# Top.net
KiCad netlist of a schematic drawn in Altium Designer
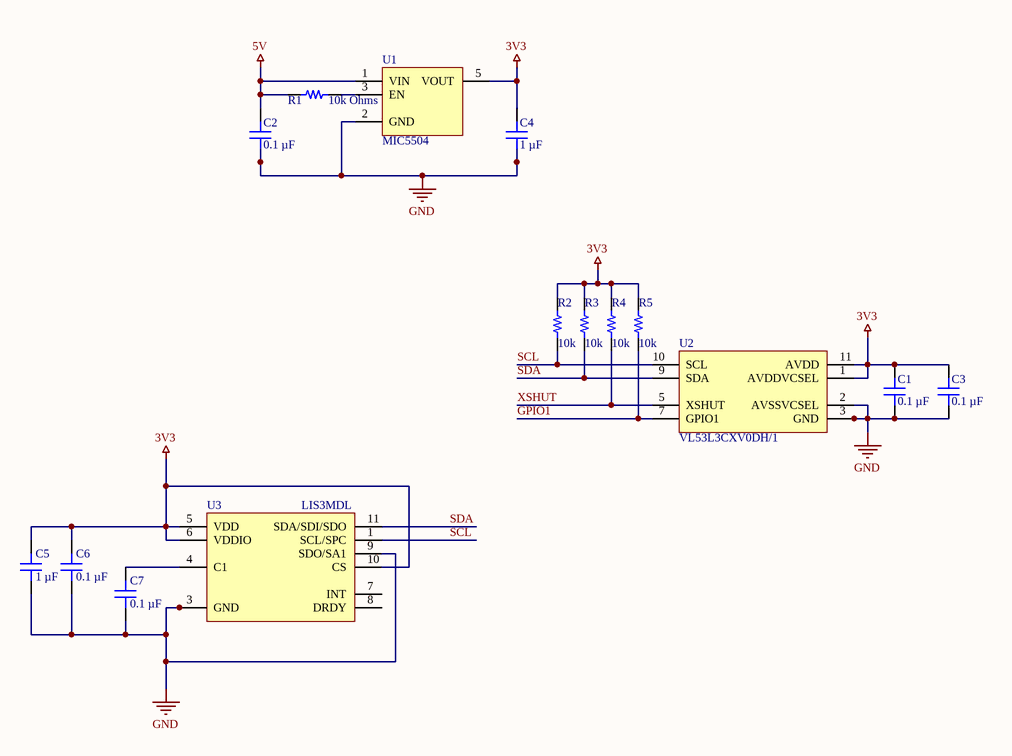
[diagram p0: Top.SchDoc]

(export (version "E")
  (design (tool "Eeschema 10.0.6"))
  (components
    (comp (ref "C1")
      (value "0.1 µF")
      (footprint "CAP 0402_1005")
      (description "CAP CER 0.1UF 16V X7R 0402")
      (fields (field (name "PART NUMBER") "C0402C104K4RACAUTO") (field (name "MANUFACTURER") "KEMET"))
      (libsource (lib "Celestial Altium Library - altium_library") (part "Capacitor"))
    )
    (comp (ref "C2")
      (value "0.1 µF")
      (footprint "CAP 0402_1005")
      (description "CAP CER 0.1UF 16V X7R 0402")
      (fields (field (name "PART NUMBER") "C0402C104K4RACAUTO") (field (name "MANUFACTURER") "KEMET"))
      (libsource (lib "Celestial Altium Library - altium_library") (part "Capacitor"))
    )
    (comp (ref "C3")
      (value "0.1 µF")
      (footprint "CAP 0402_1005")
      (description "CAP CER 0.1UF 16V X7R 0402")
      (fields (field (name "PART NUMBER") "C0402C104K4RACAUTO") (field (name "MANUFACTURER") "KEMET"))
      (libsource (lib "Celestial Altium Library - altium_library") (part "Capacitor"))
    )
    (comp (ref "C4")
      (value "1 µF")
      (footprint "CAP 0402_1005")
      (description "CAP CER 0.1UF 16V X7R 0402")
      (fields (field (name "PART NUMBER") "C0402C104K4RACAUTO") (field (name "MANUFACTURER") "KEMET"))
      (libsource (lib "Celestial Altium Library - altium_library") (part "Capacitor"))
    )
    (comp (ref "C5")
      (value "1 µF")
      (footprint "CAP 0402_1005")
      (description "CAP CER 0.1UF 16V X7R 0402")
      (fields (field (name "PART NUMBER") "C0402C104K4RACAUTO") (field (name "MANUFACTURER") "KEMET"))
      (libsource (lib "Celestial Altium Library - altium_library") (part "Capacitor"))
    )
    (comp (ref "C6")
      (value "0.1 µF")
      (footprint "CAP 0402_1005")
      (description "CAP CER 0.1UF 16V X7R 0402")
      (fields (field (name "PART NUMBER") "C0402C104K4RACAUTO") (field (name "MANUFACTURER") "KEMET"))
      (libsource (lib "Celestial Altium Library - altium_library") (part "Capacitor"))
    )
    (comp (ref "C7")
      (value "0.1 µF")
      (footprint "CAP 0402_1005")
      (description "CAP CER 0.1UF 16V X7R 0402")
      (fields (field (name "PART NUMBER") "C0402C104K4RACAUTO") (field (name "MANUFACTURER") "KEMET"))
      (libsource (lib "Celestial Altium Library - altium_library") (part "Capacitor"))
    )
    (comp (ref "R1")
      (value "10k Ohms")
      (footprint "RES 0402_1005")
      (description "RES 330 OHM 5% 1/16W 0402")
      (fields (field (name "PART NUMBER") "CRCW0402330RJNEDC") (field (name "MANUFACTURER") "Vishay Dale"))
      (libsource (lib "Celestial Altium Library - altium_library") (part "Resistor"))
    )
    (comp (ref "R2")
      (value "10k")
      (footprint "RES 0402_1005")
      (description "RES 330 OHM 5% 1/16W 0402")
      (fields (field (name "PART NUMBER") "CRCW0402330RJNEDC") (field (name "MANUFACTURER") "Vishay Dale"))
      (libsource (lib "Celestial Altium Library - altium_library") (part "Resistor"))
    )
    (comp (ref "R3")
      (value "10k")
      (footprint "RES 0402_1005")
      (description "RES 330 OHM 5% 1/16W 0402")
      (fields (field (name "PART NUMBER") "CRCW0402330RJNEDC") (field (name "MANUFACTURER") "Vishay Dale"))
      (libsource (lib "Celestial Altium Library - altium_library") (part "Resistor"))
    )
    (comp (ref "R4")
      (value "10k")
      (footprint "RES 0402_1005")
      (description "RES 330 OHM 5% 1/16W 0402")
      (fields (field (name "PART NUMBER") "CRCW0402330RJNEDC") (field (name "MANUFACTURER") "Vishay Dale"))
      (libsource (lib "Celestial Altium Library - altium_library") (part "Resistor"))
    )
    (comp (ref "R5")
      (value "10k")
      (footprint "RES 0402_1005")
      (description "RES 330 OHM 5% 1/16W 0402")
      (fields (field (name "PART NUMBER") "CRCW0402330RJNEDC") (field (name "MANUFACTURER") "Vishay Dale"))
      (libsource (lib "Celestial Altium Library - altium_library") (part "Resistor"))
    )
    (comp (ref "U1")
      (value "MIC5504")
      (footprint "TI SOT-23-5 DBV")
      (description "3.3V LDO")
      (libsource (lib "IC") (part "MIC5504-3.3YM5"))
    )
    (comp (ref "U2")
      (value "VL53L3CXV0DH/1")
      (footprint "XDCR_VL53L3CXV0DH/1")
      (description "Optical Sensor 118.110 (3m) I2C Output")
      (fields (field (name "MF") "STMicroelectronics"))
      (libsource (lib "IC") (part "VL53L3CXV0DH/1"))
    )
    (comp (ref "U3")
      (value "LIS3MDL")
      (footprint "LGA12_ST")
      (description "Magnetometer")
      (libsource (lib "IC") (part "LIS3MDL"))
    )
  )
  (nets
    (net (code "1") (name "/GPIO1") (class "Default")
      (node (ref "R5") (pin "2") (pinfunction "2_2") (pintype "passive"))
      (node (ref "U2") (pin "7") (pinfunction "GPIO1_7") (pintype "passive"))
    )
    (net (code "2") (name "/SCL") (class "Default")
      (node (ref "R2") (pin "2") (pinfunction "2_2") (pintype "passive"))
      (node (ref "U2") (pin "10") (pinfunction "SCL_10") (pintype "passive"))
      (node (ref "U3") (pin "1") (pinfunction "SCL/SPC_1") (pintype "passive"))
    )
    (net (code "3") (name "/SDA") (class "Default")
      (node (ref "R3") (pin "2") (pinfunction "2_2") (pintype "passive"))
      (node (ref "U2") (pin "9") (pinfunction "SDA_9") (pintype "passive"))
      (node (ref "U3") (pin "11") (pinfunction "SDA/SDI/SDO_11") (pintype "passive"))
    )
    (net (code "4") (name "/XSHUT") (class "Default")
      (node (ref "R4") (pin "2") (pinfunction "2_2") (pintype "passive"))
      (node (ref "U2") (pin "5") (pinfunction "XSHUT_5") (pintype "passive"))
    )
    (net (code "5") (name "3V3") (class "Default")
      (node (ref "C1") (pin "2") (pinfunction "2_2") (pintype "passive"))
      (node (ref "C3") (pin "2") (pinfunction "2_2") (pintype "passive"))
      (node (ref "C4") (pin "2") (pinfunction "2_2") (pintype "passive"))
      (node (ref "C5") (pin "1") (pinfunction "1_1") (pintype "passive"))
      (node (ref "C6") (pin "1") (pinfunction "1_1") (pintype "passive"))
      (node (ref "R2") (pin "1") (pinfunction "1_1") (pintype "passive"))
      (node (ref "R3") (pin "1") (pinfunction "1_1") (pintype "passive"))
      (node (ref "R4") (pin "1") (pinfunction "1_1") (pintype "passive"))
      (node (ref "R5") (pin "1") (pinfunction "1_1") (pintype "passive"))
      (node (ref "U1") (pin "5") (pinfunction "VOUT_5") (pintype "passive"))
      (node (ref "U2") (pin "1") (pinfunction "AVDDVCSEL_1") (pintype "passive"))
      (node (ref "U2") (pin "11") (pinfunction "AVDD_11") (pintype "passive"))
      (node (ref "U3") (pin "10") (pinfunction "CS_10") (pintype "passive"))
      (node (ref "U3") (pin "5") (pinfunction "VDD_5") (pintype "passive"))
      (node (ref "U3") (pin "6") (pinfunction "VDDIO_6") (pintype "passive"))
    )
    (net (code "6") (name "5V") (class "Default")
      (node (ref "C2") (pin "2") (pinfunction "2_2") (pintype "passive"))
      (node (ref "R1") (pin "2") (pinfunction "2_2") (pintype "passive"))
      (node (ref "U1") (pin "1") (pinfunction "VIN_1") (pintype "passive"))
    )
    (net (code "7") (name "GND") (class "Default")
      (node (ref "C1") (pin "1") (pinfunction "1_1") (pintype "passive"))
      (node (ref "C2") (pin "1") (pinfunction "1_1") (pintype "passive"))
      (node (ref "C3") (pin "1") (pinfunction "1_1") (pintype "passive"))
      (node (ref "C4") (pin "1") (pinfunction "1_1") (pintype "passive"))
      (node (ref "C5") (pin "2") (pinfunction "2_2") (pintype "passive"))
      (node (ref "C6") (pin "2") (pinfunction "2_2") (pintype "passive"))
      (node (ref "C7") (pin "2") (pinfunction "2_2") (pintype "passive"))
      (node (ref "U1") (pin "2") (pinfunction "GND_2") (pintype "passive"))
      (node (ref "U2") (pin "12") (pinfunction "GND_12") (pintype "passive"))
      (node (ref "U2") (pin "2") (pinfunction "AVSSVCSEL_2") (pintype "passive"))
      (node (ref "U2") (pin "3") (pinfunction "GND_3") (pintype "power_in"))
      (node (ref "U2") (pin "4") (pinfunction "GND_4") (pintype "power_in"))
      (node (ref "U2") (pin "6") (pinfunction "GND_6") (pintype "power_in"))
      (node (ref "U3") (pin "12") (pinfunction "Reserved_12") (pintype "passive"))
      (node (ref "U3") (pin "2") (pinfunction "Reserved_2") (pintype "passive"))
      (node (ref "U3") (pin "3") (pinfunction "GND_3") (pintype "passive"))
      (node (ref "U3") (pin "9") (pinfunction "SDO/SA1_9") (pintype "passive"))
    )
    (net (code "8") (name "Net-(U1-EN)") (class "Default")
      (node (ref "R1") (pin "1") (pinfunction "1_1") (pintype "passive"))
      (node (ref "U1") (pin "3") (pinfunction "EN_3") (pintype "passive"))
    )
    (net (code "9") (name "Net-(U3-C1)") (class "Default")
      (node (ref "C7") (pin "1") (pinfunction "1_1") (pintype "passive"))
      (node (ref "U3") (pin "4") (pinfunction "C1_4") (pintype "passive"))
    )
    (net (code "10") (name "unconnected-(U3-DRDY-Pad8)") (class "Default")
      (node (ref "U3") (pin "8") (pinfunction "DRDY_8") (pintype "passive"))
    )
    (net (code "11") (name "unconnected-(U3-INT-Pad7)") (class "Default")
      (node (ref "U3") (pin "7") (pinfunction "INT_7") (pintype "passive"))
    )
  )
)
